# mcu.net
KiCad netlist of a schematic drawn in Altium Designer
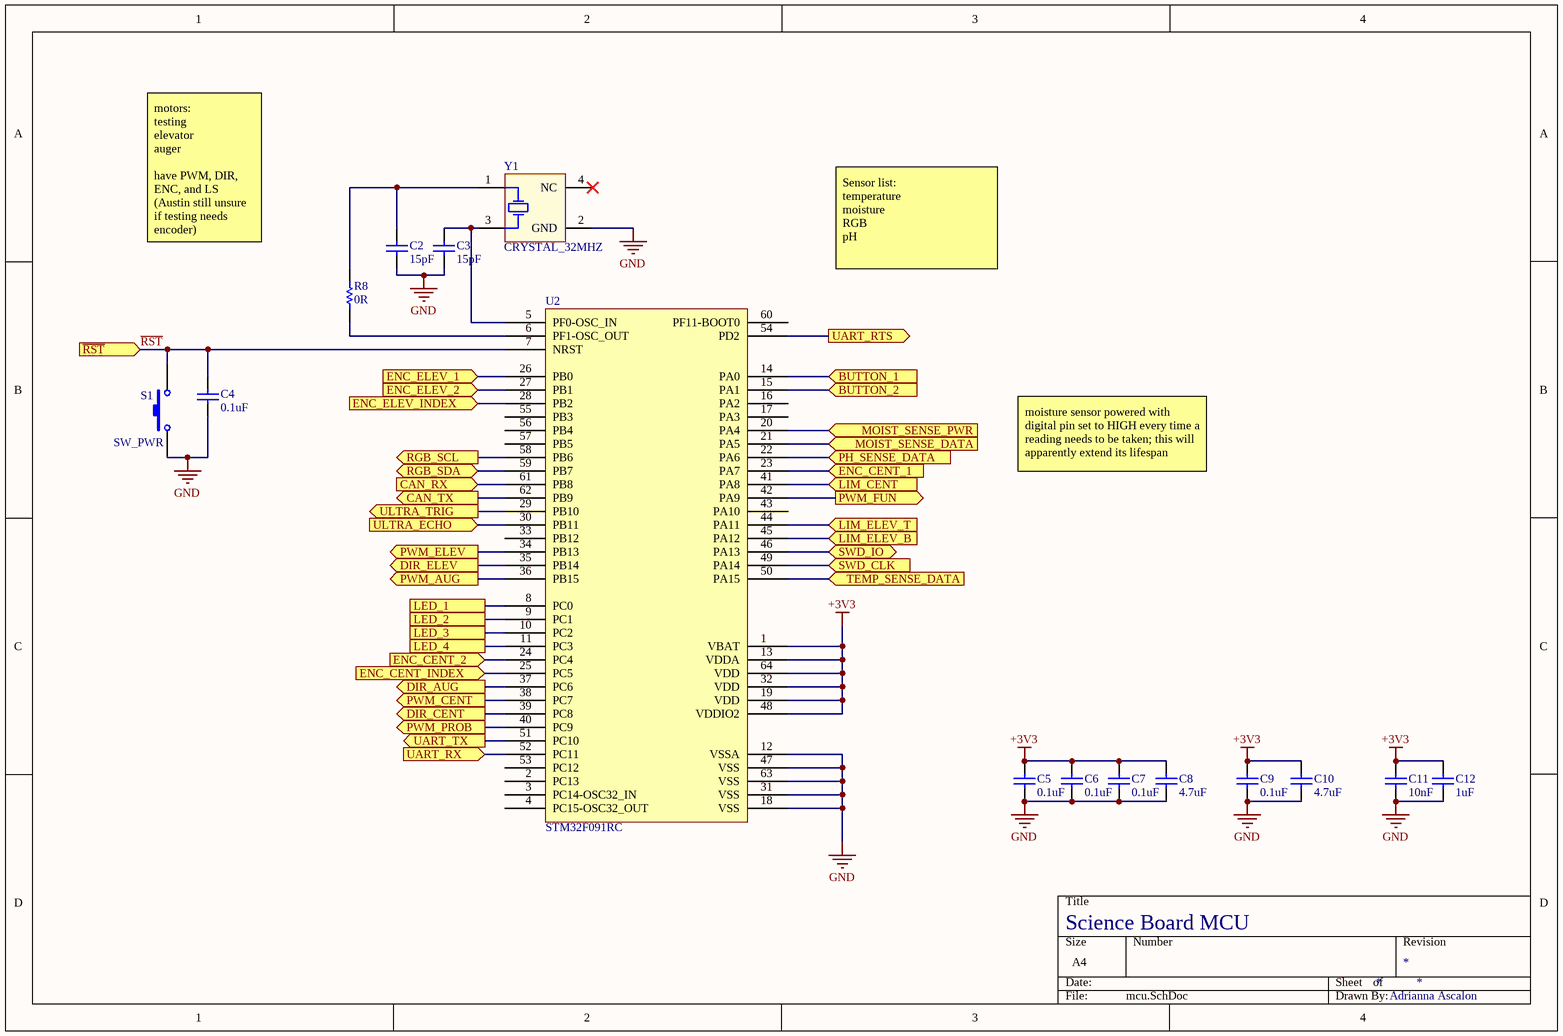
[diagram p0: mcu.SchDoc]

(export (version "E")
  (design (tool "Eeschema 10.0.6"))
  (components
    (comp (ref "C2")
      (value "15pF")
      (footprint "CAPC0603(1608)55_N")
      (description "CAP CER 15PF 250V NPO 0603")
      (fields (field (name "PART NUMBER") "AC0603JRNPOYBN150") (field (name "MANUFACTURER") "Yageo"))
      (libsource (lib "UWRT_Schematic_Library_2019") (part "CAP_15pF_0603"))
    )
    (comp (ref "C3")
      (value "15pF")
      (footprint "CAPC0603(1608)55_N")
      (description "CAP CER 15PF 250V NPO 0603")
      (fields (field (name "PART NUMBER") "AC0603JRNPOYBN150") (field (name "MANUFACTURER") "Yageo"))
      (libsource (lib "UWRT_Schematic_Library_2019") (part "CAP_15pF_0603"))
    )
    (comp (ref "C4")
      (value "0.1uF")
      (footprint "CAPC0603(1608)55_N")
      (description "CAP CER 0.1UF 16V X7R 0603")
      (fields (field (name "PART NUMBER") "CC0603KRX7R7BB104") (field (name "MANUFACTURER") "Yageo"))
      (libsource (lib "UWRT_Schematic_Library_2019") (part "CAP_0.1uF_16V_0603"))
    )
    (comp (ref "C5")
      (value "0.1uF")
      (footprint "CAPC0603(1608)55_N")
      (description "CAP CER 0.1UF 16V X7R 0603")
      (fields (field (name "PART NUMBER") "CC0603KRX7R7BB104") (field (name "MANUFACTURER") "Yageo"))
      (libsource (lib "UWRT_Schematic_Library_2019") (part "CAP_0.1uF_16V_0603"))
    )
    (comp (ref "C6")
      (value "0.1uF")
      (footprint "CAPC0603(1608)55_N")
      (description "CAP CER 0.1UF 16V X7R 0603")
      (fields (field (name "PART NUMBER") "CC0603KRX7R7BB104") (field (name "MANUFACTURER") "Yageo"))
      (libsource (lib "UWRT_Schematic_Library_2019") (part "CAP_0.1uF_16V_0603"))
    )
    (comp (ref "C7")
      (value "0.1uF")
      (footprint "CAPC0603(1608)55_N")
      (description "CAP CER 0.1UF 16V X7R 0603")
      (fields (field (name "PART NUMBER") "CC0603KRX7R7BB104") (field (name "MANUFACTURER") "Yageo"))
      (libsource (lib "UWRT_Schematic_Library_2019") (part "CAP_0.1uF_16V_0603"))
    )
    (comp (ref "C8")
      (value "4.7uF")
      (footprint "CAPC0603(1608)55_N")
      (description "CAP CER 4.7UF 6.3V X5R 0603")
      (fields (field (name "PART NUMBER") "CC0603KRX5R5BB475") (field (name "MANUFACTURER") "Yageo"))
      (libsource (lib "UWRT_Schematic_Library_2019") (part "CAP_4.7uF_0603"))
    )
    (comp (ref "C9")
      (value "0.1uF")
      (footprint "CAPC0603(1608)55_N")
      (description "CAP CER 0.1UF 16V X7R 0603")
      (fields (field (name "PART NUMBER") "CC0603KRX7R7BB104") (field (name "MANUFACTURER") "Yageo"))
      (libsource (lib "UWRT_Schematic_Library_2019") (part "CAP_0.1uF_16V_0603"))
    )
    (comp (ref "C10")
      (value "4.7uF")
      (footprint "CAPC0603(1608)55_N")
      (description "CAP CER 4.7UF 6.3V X5R 0603")
      (fields (field (name "PART NUMBER") "CC0603KRX5R5BB475") (field (name "MANUFACTURER") "Yageo"))
      (libsource (lib "UWRT_Schematic_Library_2019") (part "CAP_4.7uF_0603"))
    )
    (comp (ref "C11")
      (value "10nF")
      (footprint "CAPC0603(1608)55_N")
      (description "CAP CER 10000PF 16V X7R 0603")
      (fields (field (name "PART NUMBER") "CC0603KRX7R7BB103") (field (name "MANUFACTURER") "Yageo"))
      (libsource (lib "UWRT_Schematic_Library_2019") (part "CAP_10nF_0603"))
    )
    (comp (ref "C12")
      (value "1uF")
      (footprint "CAPC0603(1608)55_N")
      (description "CAP CER 1UF 16V Y5V 0603")
      (fields (field (name "PART NUMBER") "CC0603ZRY5V7BB105") (field (name "MANUFACTURER") "Yageo"))
      (libsource (lib "UWRT_Schematic_Library_2019") (part "CAP_1uF_16V_0603"))
    )
    (comp (ref "R8")
      (value "0R")
      (footprint "RESC0603(1608)_N")
      (description "RES SMD 0 OHM JUMPER 1/10W 0603")
      (fields (field (name "MANUFACTURER") "Yageo") (field (name "Comment") "RES_0R_0603"))
      (libsource (lib "UWRT_Schematic_Library_2019") (part "RES_0R_0603"))
    )
    (comp (ref "S1")
      (value "SW_PWR")
      (footprint "PTS830GM140")
      (description "Power Switch (Red)")
      (fields (field (name "PART NUMBER") "PTS830GM140 SMTR LFS"))
      (libsource (lib "UWRT_Schematic_Library_2019") (part "SW_PWR"))
    )
    (comp (ref "U2")
      (value "STM32F091RC")
      (footprint "UWRT_Footprint_Library_2019:STM_LQFP64_N")
      (fields (field (name "MANUFACTURER") "STMicroelectronics"))
      (libsource (lib "UWRT_Schematic_Library_2019") (part "STM32F091RC"))
    )
    (comp (ref "Y1")
      (value "CRYSTAL_32MHZ")
      (footprint "AVX-CX2520DB32000D0GEJZ1-4_V")
      (description "CRYSTAL 32MHZ 8PF SMD")
      (fields
        (field (name "PART NUMBER") "CX2520DB32000D0GPSC1")
        (field (name "MANUFACTURER") "Kyocera International Inc. Electronic Components")
      )
      (libsource (lib "UWRT_Schematic_Library_2019") (part "CRYSTAL_32MHZ"))
    )
  )
  (nets
    (net (code "1") (name "+3V3") (class "Default")
      (node (ref "C10") (pin "2") (pinfunction "2_2") (pintype "passive"))
      (node (ref "C11") (pin "2") (pinfunction "2_2") (pintype "passive"))
      (node (ref "C12") (pin "2") (pinfunction "2_2") (pintype "passive"))
      (node (ref "C5") (pin "1") (pinfunction "1_1") (pintype "passive"))
      (node (ref "C6") (pin "1") (pinfunction "1_1") (pintype "passive"))
      (node (ref "C7") (pin "1") (pinfunction "1_1") (pintype "passive"))
      (node (ref "C8") (pin "2") (pinfunction "2_2") (pintype "passive"))
      (node (ref "C9") (pin "1") (pinfunction "1_1") (pintype "passive"))
      (node (ref "U2") (pin "1") (pinfunction "VBAT_1") (pintype "passive"))
      (node (ref "U2") (pin "13") (pinfunction "VDDA_13") (pintype "passive"))
      (node (ref "U2") (pin "19") (pinfunction "VDD_19") (pintype "passive"))
      (node (ref "U2") (pin "32") (pinfunction "VDD_32") (pintype "passive"))
      (node (ref "U2") (pin "48") (pinfunction "VDDIO2_48") (pintype "passive"))
      (node (ref "U2") (pin "64") (pinfunction "VDD_64") (pintype "passive"))
    )
    (net (code "2") (name "/BUTTON_1") (class "Default")
      (node (ref "U2") (pin "14") (pinfunction "PA0_14") (pintype "passive"))
    )
    (net (code "3") (name "/BUTTON_2") (class "Default")
      (node (ref "U2") (pin "15") (pinfunction "PA1_15") (pintype "passive"))
    )
    (net (code "4") (name "/CAN_RX") (class "Default")
      (node (ref "U2") (pin "61") (pinfunction "PB8_61") (pintype "passive"))
    )
    (net (code "5") (name "/CAN_TX") (class "Default")
      (node (ref "U2") (pin "62") (pinfunction "PB9_62") (pintype "passive"))
    )
    (net (code "6") (name "/DIR_AUG") (class "Default")
      (node (ref "U2") (pin "37") (pinfunction "PC6_37") (pintype "passive"))
    )
    (net (code "7") (name "/DIR_CENT") (class "Default")
      (node (ref "U2") (pin "39") (pinfunction "PC8_39") (pintype "passive"))
    )
    (net (code "8") (name "/DIR_ELEV") (class "Default")
      (node (ref "U2") (pin "35") (pinfunction "PB14_35") (pintype "passive"))
    )
    (net (code "9") (name "/ENC_CENT_1") (class "Default")
      (node (ref "U2") (pin "23") (pinfunction "PA7_23") (pintype "passive"))
    )
    (net (code "10") (name "/ENC_CENT_2") (class "Default")
      (node (ref "U2") (pin "24") (pinfunction "PC4_24") (pintype "passive"))
    )
    (net (code "11") (name "/ENC_CENT_INDEX") (class "Default")
      (node (ref "U2") (pin "25") (pinfunction "PC5_25") (pintype "passive"))
    )
    (net (code "12") (name "/ENC_ELEV_1") (class "Default")
      (node (ref "U2") (pin "26") (pinfunction "PB0_26") (pintype "passive"))
    )
    (net (code "13") (name "/ENC_ELEV_2") (class "Default")
      (node (ref "U2") (pin "27") (pinfunction "PB1_27") (pintype "passive"))
    )
    (net (code "14") (name "/ENC_ELEV_INDEX") (class "Default")
      (node (ref "U2") (pin "28") (pinfunction "PB2_28") (pintype "passive"))
    )
    (net (code "15") (name "/LED_1") (class "Default")
      (node (ref "U2") (pin "8") (pinfunction "PC0_8") (pintype "passive"))
    )
    (net (code "16") (name "/LED_2") (class "Default")
      (node (ref "U2") (pin "9") (pinfunction "PC1_9") (pintype "passive"))
    )
    (net (code "17") (name "/LED_3") (class "Default")
      (node (ref "U2") (pin "10") (pinfunction "PC2_10") (pintype "passive"))
    )
    (net (code "18") (name "/LED_4") (class "Default")
      (node (ref "U2") (pin "11") (pinfunction "PC3_11") (pintype "passive"))
    )
    (net (code "19") (name "/LIM_CENT") (class "Default")
      (node (ref "U2") (pin "41") (pinfunction "PA8_41") (pintype "passive"))
    )
    (net (code "20") (name "/LIM_ELEV_B") (class "Default")
      (node (ref "U2") (pin "45") (pinfunction "PA12_45") (pintype "passive"))
    )
    (net (code "21") (name "/LIM_ELEV_T") (class "Default")
      (node (ref "U2") (pin "44") (pinfunction "PA11_44") (pintype "passive"))
    )
    (net (code "22") (name "/MOIST_SENSE_DATA") (class "Default")
      (node (ref "U2") (pin "21") (pinfunction "PA5_21") (pintype "passive"))
    )
    (net (code "23") (name "/MOIST_SENSE_PWR") (class "Default")
      (node (ref "U2") (pin "20") (pinfunction "PA4_20") (pintype "passive"))
    )
    (net (code "24") (name "/PH_SENSE_DATA") (class "Default")
      (node (ref "U2") (pin "22") (pinfunction "PA6_22") (pintype "passive"))
    )
    (net (code "25") (name "/PWM_AUG") (class "Default")
      (node (ref "U2") (pin "36") (pinfunction "PB15_36") (pintype "passive"))
    )
    (net (code "26") (name "/PWM_CENT") (class "Default")
      (node (ref "U2") (pin "38") (pinfunction "PC7_38") (pintype "passive"))
    )
    (net (code "27") (name "/PWM_ELEV") (class "Default")
      (node (ref "U2") (pin "34") (pinfunction "PB13_34") (pintype "passive"))
    )
    (net (code "28") (name "/PWM_FUN") (class "Default")
      (node (ref "U2") (pin "42") (pinfunction "PA9_42") (pintype "passive"))
    )
    (net (code "29") (name "/PWM_PROB") (class "Default")
      (node (ref "U2") (pin "40") (pinfunction "PC9_40") (pintype "passive"))
    )
    (net (code "30") (name "/RGB_SCL") (class "Default")
      (node (ref "U2") (pin "58") (pinfunction "PB6_58") (pintype "passive"))
    )
    (net (code "31") (name "/RGB_SDA") (class "Default")
      (node (ref "U2") (pin "59") (pinfunction "PB7_59") (pintype "passive"))
    )
    (net (code "32") (name "/SWD_CLK") (class "Default")
      (node (ref "U2") (pin "49") (pinfunction "PA14_49") (pintype "passive"))
    )
    (net (code "33") (name "/SWD_IO") (class "Default")
      (node (ref "U2") (pin "46") (pinfunction "PA13_46") (pintype "passive"))
    )
    (net (code "34") (name "/TEMP_SENSE_DATA") (class "Default")
      (node (ref "U2") (pin "50") (pinfunction "PA15_50") (pintype "passive"))
    )
    (net (code "35") (name "/UART_RTS") (class "Default")
      (node (ref "U2") (pin "54") (pinfunction "PD2_54") (pintype "passive"))
    )
    (net (code "36") (name "/UART_RX") (class "Default")
      (node (ref "U2") (pin "52") (pinfunction "PC11_52") (pintype "passive"))
    )
    (net (code "37") (name "/UART_TX") (class "Default")
      (node (ref "U2") (pin "51") (pinfunction "PC10_51") (pintype "passive"))
    )
    (net (code "38") (name "/ULTRA_ECHO") (class "Default")
      (node (ref "U2") (pin "30") (pinfunction "PB11_30") (pintype "passive"))
    )
    (net (code "39") (name "/ULTRA_TRIG") (class "Default")
      (node (ref "U2") (pin "29") (pinfunction "PB10_29") (pintype "passive"))
    )
    (net (code "40") (name "/~{RST}") (class "Default")
      (node (ref "C4") (pin "2") (pinfunction "2_2") (pintype "passive"))
      (node (ref "S1") (pin "2") (pinfunction "2_2") (pintype "passive"))
      (node (ref "U2") (pin "7") (pinfunction "NRST_7") (pintype "passive"))
    )
    (net (code "41") (name "GND") (class "Default")
      (node (ref "C10") (pin "1") (pinfunction "1_1") (pintype "passive"))
      (node (ref "C11") (pin "1") (pinfunction "1_1") (pintype "passive"))
      (node (ref "C12") (pin "1") (pinfunction "1_1") (pintype "passive"))
      (node (ref "C2") (pin "1") (pinfunction "1_1") (pintype "passive"))
      (node (ref "C3") (pin "1") (pinfunction "1_1") (pintype "passive"))
      (node (ref "C4") (pin "1") (pinfunction "1_1") (pintype "passive"))
      (node (ref "C5") (pin "2") (pinfunction "2_2") (pintype "passive"))
      (node (ref "C6") (pin "2") (pinfunction "2_2") (pintype "passive"))
      (node (ref "C7") (pin "2") (pinfunction "2_2") (pintype "passive"))
      (node (ref "C8") (pin "1") (pinfunction "1_1") (pintype "passive"))
      (node (ref "C9") (pin "2") (pinfunction "2_2") (pintype "passive"))
      (node (ref "S1") (pin "1") (pinfunction "1_1") (pintype "passive"))
      (node (ref "U2") (pin "12") (pinfunction "VSSA_12") (pintype "passive"))
      (node (ref "U2") (pin "18") (pinfunction "VSS_18") (pintype "passive"))
      (node (ref "U2") (pin "31") (pinfunction "VSS_31") (pintype "passive"))
      (node (ref "U2") (pin "47") (pinfunction "VSS_47") (pintype "passive"))
      (node (ref "U2") (pin "63") (pinfunction "VSS_63") (pintype "passive"))
      (node (ref "Y1") (pin "2") (pinfunction "GND_2") (pintype "power_in"))
    )
    (net (code "42") (name "Net-(C2-Pad2)") (class "Default")
      (node (ref "C2") (pin "2") (pinfunction "2_2") (pintype "passive"))
      (node (ref "R8") (pin "2") (pinfunction "2_2") (pintype "passive"))
      (node (ref "Y1") (pin "1") (pinfunction "HOT_1") (pintype "passive"))
    )
    (net (code "43") (name "Net-(U2-PF0-OSC_IN)") (class "Default")
      (node (ref "C3") (pin "2") (pinfunction "2_2") (pintype "passive"))
      (node (ref "U2") (pin "5") (pinfunction "PF0-OSC_IN_5") (pintype "passive"))
      (node (ref "Y1") (pin "3") (pinfunction "HOT_3") (pintype "passive"))
    )
    (net (code "44") (name "Net-(U2-PF1-OSC_OUT)") (class "Default")
      (node (ref "R8") (pin "1") (pinfunction "1_1") (pintype "passive"))
      (node (ref "U2") (pin "6") (pinfunction "PF1-OSC_OUT_6") (pintype "passive"))
    )
    (net (code "45") (name "unconnected-(U2-PA2-Pad16)") (class "Default")
      (node (ref "U2") (pin "16") (pinfunction "PA2_16") (pintype "passive"))
    )
    (net (code "46") (name "unconnected-(U2-PA3-Pad17)") (class "Default")
      (node (ref "U2") (pin "17") (pinfunction "PA3_17") (pintype "passive"))
    )
    (net (code "47") (name "unconnected-(U2-PA10-Pad43)") (class "Default")
      (node (ref "U2") (pin "43") (pinfunction "PA10_43") (pintype "passive"))
    )
    (net (code "48") (name "unconnected-(U2-PB3-Pad55)") (class "Default")
      (node (ref "U2") (pin "55") (pinfunction "PB3_55") (pintype "passive"))
    )
    (net (code "49") (name "unconnected-(U2-PB4-Pad56)") (class "Default")
      (node (ref "U2") (pin "56") (pinfunction "PB4_56") (pintype "passive"))
    )
    (net (code "50") (name "unconnected-(U2-PB5-Pad57)") (class "Default")
      (node (ref "U2") (pin "57") (pinfunction "PB5_57") (pintype "passive"))
    )
    (net (code "51") (name "unconnected-(U2-PB12-Pad33)") (class "Default")
      (node (ref "U2") (pin "33") (pinfunction "PB12_33") (pintype "passive"))
    )
    (net (code "52") (name "unconnected-(U2-PC12-Pad53)") (class "Default")
      (node (ref "U2") (pin "53") (pinfunction "PC12_53") (pintype "passive"))
    )
    (net (code "53") (name "unconnected-(U2-PC13-Pad2)") (class "Default")
      (node (ref "U2") (pin "2") (pinfunction "PC13_2") (pintype "passive"))
    )
    (net (code "54") (name "unconnected-(U2-PC14-OSC32_IN-Pad3)") (class "Default")
      (node (ref "U2") (pin "3") (pinfunction "PC14-OSC32_IN_3") (pintype "passive"))
    )
    (net (code "55") (name "unconnected-(U2-PC15-OSC32_OUT-Pad4)") (class "Default")
      (node (ref "U2") (pin "4") (pinfunction "PC15-OSC32_OUT_4") (pintype "passive"))
    )
    (net (code "56") (name "unconnected-(U2-PF11-BOOT0-Pad60)") (class "Default")
      (node (ref "U2") (pin "60") (pinfunction "PF11-BOOT0_60") (pintype "passive"))
    )
    (net (code "57") (name "unconnected-(Y1-NC-Pad4)") (class "Default")
      (node (ref "Y1") (pin "4") (pinfunction "NC_4") (pintype "passive+no_connect"))
    )
  )
)
